# LDO.net
KiCad netlist of a schematic drawn in Altium Designer
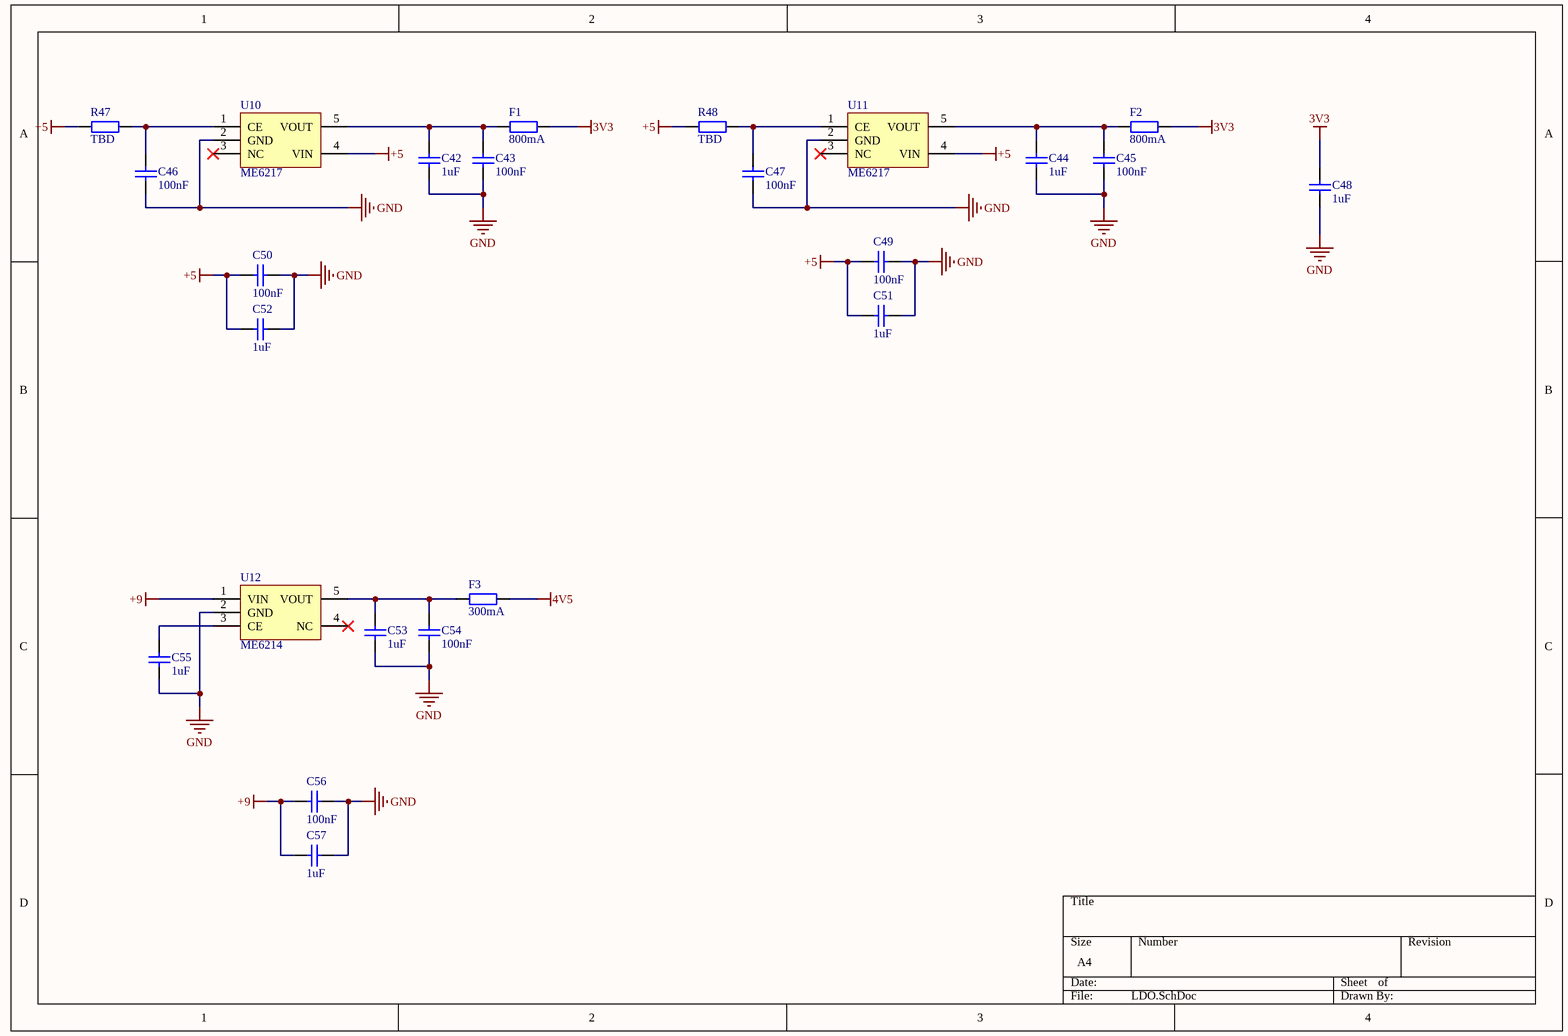
[diagram p0: LDO.SchDoc]

(export (version "E")
  (design (tool "Eeschema 10.0.6"))
  (components
    (comp (ref "C42")
      (value "1uF")
      (footprint "C0402_NS")
      (description "Capacitance 0402")
      (libsource (lib "AxisQuad Components Lib") (part "C0402"))
    )
    (comp (ref "C43")
      (value "100nF")
      (footprint "C0402_NS")
      (description "Capacitance 0402")
      (libsource (lib "AxisQuad Components Lib") (part "C0402"))
    )
    (comp (ref "C44")
      (value "1uF")
      (footprint "C0402_NS")
      (description "Capacitance 0402")
      (libsource (lib "AxisQuad Components Lib") (part "C0402"))
    )
    (comp (ref "C45")
      (value "100nF")
      (footprint "C0402_NS")
      (description "Capacitance 0402")
      (libsource (lib "AxisQuad Components Lib") (part "C0402"))
    )
    (comp (ref "C46")
      (value "100nF")
      (footprint "C0402_NS")
      (description "Capacitance 0402")
      (libsource (lib "AxisQuad Components Lib") (part "C0402"))
    )
    (comp (ref "C47")
      (value "100nF")
      (footprint "C0402_NS")
      (description "Capacitance 0402")
      (libsource (lib "AxisQuad Components Lib") (part "C0402"))
    )
    (comp (ref "C48") (value "1uF") (footprint "C3216_NS") (libsource (lib "DBS Components Lib") (part "C")))
    (comp (ref "C49")
      (value "100nF")
      (footprint "C0402_NS")
      (description "Capacitance 0402")
      (libsource (lib "AxisQuad Components Lib") (part "C0402"))
    )
    (comp (ref "C50")
      (value "100nF")
      (footprint "C0402_NS")
      (description "Capacitance 0402")
      (libsource (lib "AxisQuad Components Lib") (part "C0402"))
    )
    (comp (ref "C51")
      (value "1uF")
      (footprint "C0402_NS")
      (description "Capacitance 0402")
      (libsource (lib "AxisQuad Components Lib") (part "C0402"))
    )
    (comp (ref "C52")
      (value "1uF")
      (footprint "C0402_NS")
      (description "Capacitance 0402")
      (libsource (lib "AxisQuad Components Lib") (part "C0402"))
    )
    (comp (ref "C53") (value "1uF") (footprint "C3216_NS") (libsource (lib "DBS Components Lib") (part "C")))
    (comp (ref "C54")
      (value "100nF")
      (footprint "C0402_NS")
      (description "Capacitance 0402")
      (libsource (lib "AxisQuad Components Lib") (part "C0402"))
    )
    (comp (ref "C55")
      (value "1uF")
      (footprint "C0402_NS")
      (description "Capacitance 0402")
      (libsource (lib "AxisQuad Components Lib") (part "C0402"))
    )
    (comp (ref "C56")
      (value "100nF")
      (footprint "C0402_NS")
      (description "Capacitance 0402")
      (libsource (lib "AxisQuad Components Lib") (part "C0402"))
    )
    (comp (ref "C57")
      (value "1uF")
      (footprint "C0402_NS")
      (description "Capacitance 0402")
      (libsource (lib "AxisQuad Components Lib") (part "C0402"))
    )
    (comp (ref "F1")
      (value "800mA")
      (footprint "R0603_NS")
      (description "Resistance 0603")
      (libsource (lib "Daedalus Components Lib") (part "R0603"))
    )
    (comp (ref "F2")
      (value "800mA")
      (footprint "R0603_NS")
      (description "Resistance 0603")
      (libsource (lib "Daedalus Components Lib") (part "R0603"))
    )
    (comp (ref "F3")
      (value "300mA")
      (footprint "R0603_NS")
      (description "Resistance 0603")
      (libsource (lib "DBS Components Lib") (part "R0603"))
    )
    (comp (ref "R47")
      (value "TBD")
      (footprint "R0402_NS")
      (description "Resistance 0402")
      (libsource (lib "DBS Components Lib") (part "R0402"))
    )
    (comp (ref "R48")
      (value "TBD")
      (footprint "R0402_NS")
      (description "Resistance 0402")
      (libsource (lib "DBS Components Lib") (part "R0402"))
    )
    (comp (ref "U10")
      (value "ME6217")
      (footprint "SOT23-5")
      (libsource (lib "Daedalus Components Lib") (part "ME6217"))
    )
    (comp (ref "U11")
      (value "ME6217")
      (footprint "SOT23-5")
      (libsource (lib "Daedalus Components Lib") (part "ME6217"))
    )
    (comp (ref "U12")
      (value "ME6214")
      (footprint "SOT23-5")
      (libsource (lib "DBS Components Lib") (part "ME6214"))
    )
  )
  (nets
    (net (code "1") (name "+5") (class "Default")
      (node (ref "C49") (pin "2") (pinfunction "2_2") (pintype "passive"))
      (node (ref "C50") (pin "2") (pinfunction "2_2") (pintype "passive"))
      (node (ref "C51") (pin "2") (pinfunction "2_2") (pintype "passive"))
      (node (ref "C52") (pin "2") (pinfunction "2_2") (pintype "passive"))
      (node (ref "R47") (pin "1") (pinfunction "1_1") (pintype "passive"))
      (node (ref "R48") (pin "1") (pinfunction "1_1") (pintype "passive"))
      (node (ref "U10") (pin "4") (pinfunction "VIN_4") (pintype "passive"))
      (node (ref "U11") (pin "4") (pinfunction "VIN_4") (pintype "passive"))
    )
    (net (code "2") (name "+9") (class "Default")
      (node (ref "C56") (pin "2") (pinfunction "2_2") (pintype "passive"))
      (node (ref "C57") (pin "2") (pinfunction "2_2") (pintype "passive"))
      (node (ref "U12") (pin "1") (pinfunction "VIN_1") (pintype "passive"))
    )
    (net (code "3") (name "3V3") (class "Default")
      (node (ref "C48") (pin "2") (pinfunction "2_2") (pintype "passive"))
      (node (ref "F1") (pin "2") (pinfunction "2_2") (pintype "passive"))
      (node (ref "F2") (pin "2") (pinfunction "2_2") (pintype "passive"))
    )
    (net (code "4") (name "4V5") (class "Default")
      (node (ref "F3") (pin "2") (pinfunction "2_2") (pintype "passive"))
    )
    (net (code "5") (name "GND") (class "Default")
      (node (ref "C42") (pin "2") (pinfunction "2_2") (pintype "passive"))
      (node (ref "C43") (pin "1") (pinfunction "1_1") (pintype "passive"))
      (node (ref "C44") (pin "2") (pinfunction "2_2") (pintype "passive"))
      (node (ref "C45") (pin "1") (pinfunction "1_1") (pintype "passive"))
      (node (ref "C46") (pin "1") (pinfunction "1_1") (pintype "passive"))
      (node (ref "C47") (pin "1") (pinfunction "1_1") (pintype "passive"))
      (node (ref "C48") (pin "1") (pinfunction "1_1") (pintype "passive"))
      (node (ref "C49") (pin "1") (pinfunction "1_1") (pintype "passive"))
      (node (ref "C50") (pin "1") (pinfunction "1_1") (pintype "passive"))
      (node (ref "C51") (pin "1") (pinfunction "1_1") (pintype "passive"))
      (node (ref "C52") (pin "1") (pinfunction "1_1") (pintype "passive"))
      (node (ref "C53") (pin "1") (pinfunction "1_1") (pintype "passive"))
      (node (ref "C54") (pin "1") (pinfunction "1_1") (pintype "passive"))
      (node (ref "C55") (pin "2") (pinfunction "2_2") (pintype "passive"))
      (node (ref "C56") (pin "1") (pinfunction "1_1") (pintype "passive"))
      (node (ref "C57") (pin "1") (pinfunction "1_1") (pintype "passive"))
      (node (ref "U10") (pin "2") (pinfunction "GND_2") (pintype "passive"))
      (node (ref "U11") (pin "2") (pinfunction "GND_2") (pintype "passive"))
      (node (ref "U12") (pin "2") (pinfunction "GND_2") (pintype "passive"))
    )
    (net (code "6") (name "Net-(U10-CE)") (class "Default")
      (node (ref "C46") (pin "2") (pinfunction "2_2") (pintype "passive"))
      (node (ref "R47") (pin "2") (pinfunction "2_2") (pintype "passive"))
      (node (ref "U10") (pin "1") (pinfunction "CE_1") (pintype "passive"))
    )
    (net (code "7") (name "Net-(U10-VOUT)") (class "Default")
      (node (ref "C42") (pin "1") (pinfunction "1_1") (pintype "passive"))
      (node (ref "C43") (pin "2") (pinfunction "2_2") (pintype "passive"))
      (node (ref "F1") (pin "1") (pinfunction "1_1") (pintype "passive"))
      (node (ref "U10") (pin "5") (pinfunction "VOUT_5") (pintype "passive"))
    )
    (net (code "8") (name "Net-(U11-CE)") (class "Default")
      (node (ref "C47") (pin "2") (pinfunction "2_2") (pintype "passive"))
      (node (ref "R48") (pin "2") (pinfunction "2_2") (pintype "passive"))
      (node (ref "U11") (pin "1") (pinfunction "CE_1") (pintype "passive"))
    )
    (net (code "9") (name "Net-(U11-VOUT)") (class "Default")
      (node (ref "C44") (pin "1") (pinfunction "1_1") (pintype "passive"))
      (node (ref "C45") (pin "2") (pinfunction "2_2") (pintype "passive"))
      (node (ref "F2") (pin "1") (pinfunction "1_1") (pintype "passive"))
      (node (ref "U11") (pin "5") (pinfunction "VOUT_5") (pintype "passive"))
    )
    (net (code "10") (name "Net-(U12-CE)") (class "Default")
      (node (ref "C55") (pin "1") (pinfunction "1_1") (pintype "passive"))
      (node (ref "U12") (pin "3") (pinfunction "CE_3") (pintype "passive"))
    )
    (net (code "11") (name "Net-(U12-VOUT)") (class "Default")
      (node (ref "C53") (pin "2") (pinfunction "2_2") (pintype "passive"))
      (node (ref "C54") (pin "2") (pinfunction "2_2") (pintype "passive"))
      (node (ref "F3") (pin "1") (pinfunction "1_1") (pintype "passive"))
      (node (ref "U12") (pin "5") (pinfunction "VOUT_5") (pintype "passive"))
    )
    (net (code "12") (name "unconnected-(U10-NC-Pad3)") (class "Default")
      (node (ref "U10") (pin "3") (pinfunction "NC_3") (pintype "passive+no_connect"))
    )
    (net (code "13") (name "unconnected-(U11-NC-Pad3)") (class "Default")
      (node (ref "U11") (pin "3") (pinfunction "NC_3") (pintype "passive+no_connect"))
    )
    (net (code "14") (name "unconnected-(U12-NC-Pad4)") (class "Default")
      (node (ref "U12") (pin "4") (pinfunction "NC_4") (pintype "passive+no_connect"))
    )
  )
)
